# EEPROM_AT24.net
KiCad netlist of a schematic drawn in Altium Designer
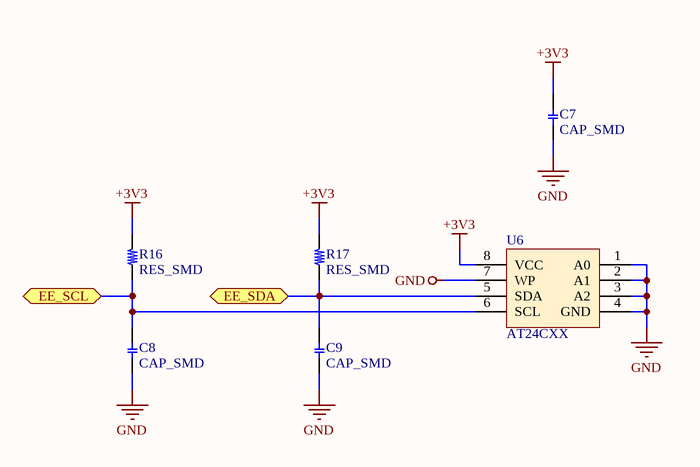
[diagram p0: EEPROM_AT24.SchDoc]

(export (version "E")
  (design (tool "Eeschema 10.0.6"))
  (components
    (comp (ref "C7")
      (value "CAP_SMD")
      (footprint "C 0603")
      (libsource (lib "radmehr_library") (part "CAP_SMD"))
    )
    (comp (ref "C8")
      (value "CAP_SMD")
      (footprint "C 0603")
      (libsource (lib "radmehr_library") (part "CAP_SMD"))
    )
    (comp (ref "C9")
      (value "CAP_SMD")
      (footprint "C 0603")
      (libsource (lib "radmehr_library") (part "CAP_SMD"))
    )
    (comp (ref "R16")
      (value "RES_SMD")
      (footprint "R 0603")
      (libsource (lib "radmehr_library") (part "RES_SMD"))
    )
    (comp (ref "R17")
      (value "RES_SMD")
      (footprint "R 0603")
      (libsource (lib "radmehr_library") (part "RES_SMD"))
    )
    (comp (ref "U6")
      (value "AT24CXX")
      (footprint "SOIC-8")
      (libsource (lib "radmehr_library") (part "AT24CXX"))
    )
  )
  (nets
    (net (code "1") (name "+3V3") (class "Default")
      (node (ref "C7") (pin "2") (pinfunction "2_2") (pintype "passive"))
      (node (ref "R16") (pin "2") (pinfunction "2_2") (pintype "passive"))
      (node (ref "R17") (pin "2") (pinfunction "2_2") (pintype "passive"))
      (node (ref "U6") (pin "8") (pinfunction "VCC_8") (pintype "passive"))
    )
    (net (code "2") (name "/EE_SCL") (class "Default")
      (node (ref "C8") (pin "2") (pinfunction "2_2") (pintype "passive"))
      (node (ref "R16") (pin "1") (pinfunction "1_1") (pintype "passive"))
      (node (ref "U6") (pin "6") (pinfunction "SCL_6") (pintype "passive"))
    )
    (net (code "3") (name "/EE_SDA") (class "Default")
      (node (ref "C9") (pin "2") (pinfunction "2_2") (pintype "passive"))
      (node (ref "R17") (pin "1") (pinfunction "1_1") (pintype "passive"))
      (node (ref "U6") (pin "5") (pinfunction "SDA_5") (pintype "passive"))
    )
    (net (code "4") (name "GND") (class "Default")
      (node (ref "C7") (pin "1") (pinfunction "1_1") (pintype "passive"))
      (node (ref "C8") (pin "1") (pinfunction "1_1") (pintype "passive"))
      (node (ref "C9") (pin "1") (pinfunction "1_1") (pintype "passive"))
      (node (ref "U6") (pin "1") (pinfunction "A0_1") (pintype "passive"))
      (node (ref "U6") (pin "2") (pinfunction "A1_2") (pintype "passive"))
      (node (ref "U6") (pin "3") (pinfunction "A2_3") (pintype "passive"))
      (node (ref "U6") (pin "4") (pinfunction "GND_4") (pintype "passive"))
      (node (ref "U6") (pin "7") (pinfunction "WP_7") (pintype "passive"))
    )
  )
)
